# Sport_Analyzer_Chronojump_Teensy_4_4_but.net
KiCad netlist of a schematic drawn in EAGLE
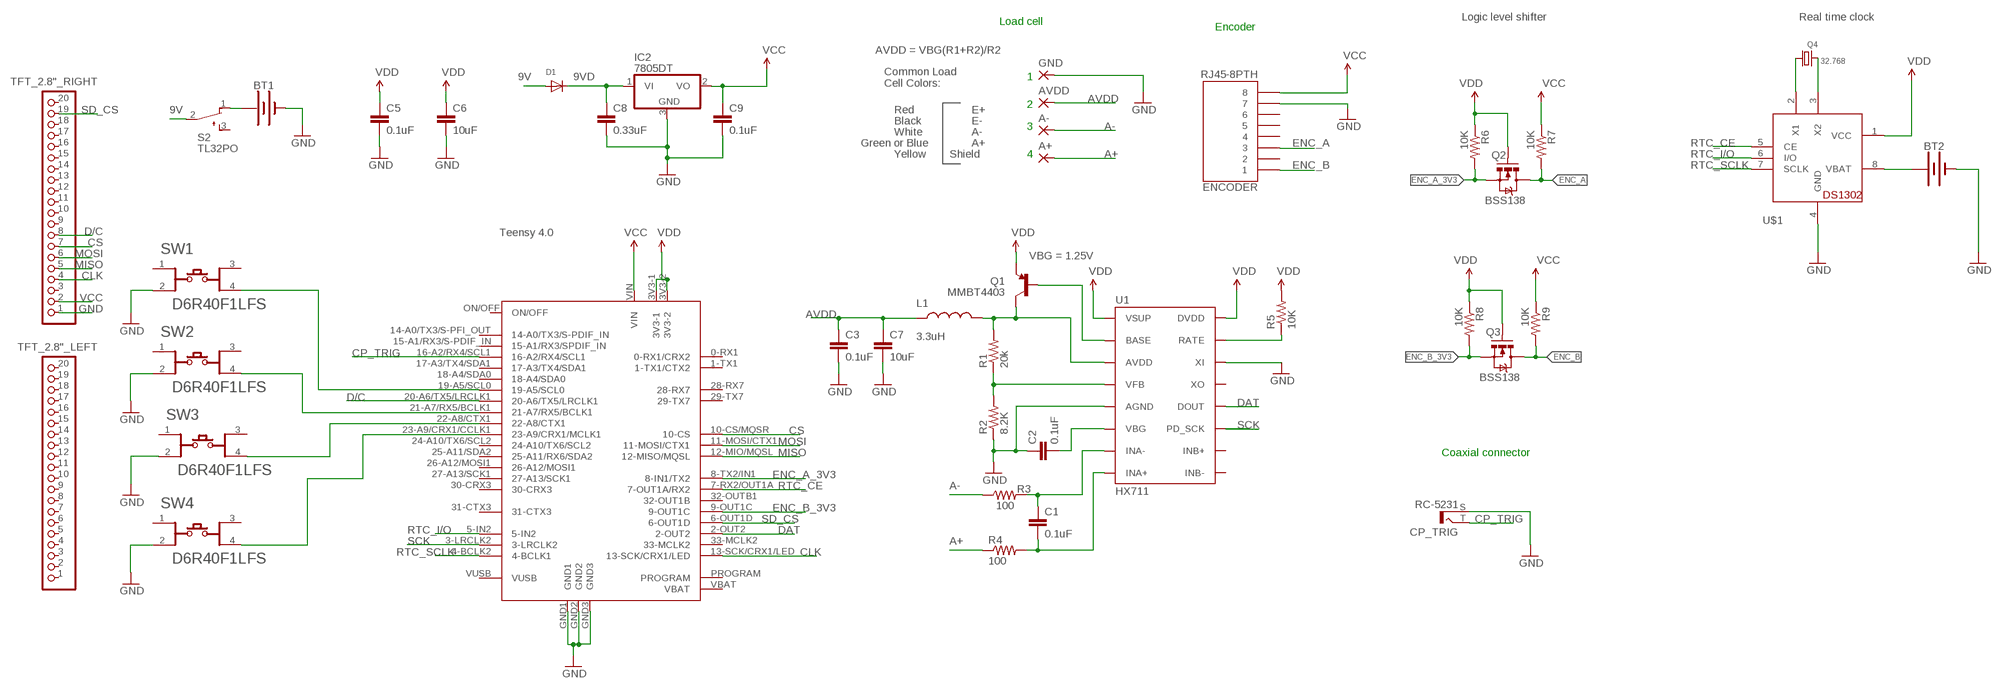
[diagram p0: schematic, sheet 1]

(export (version "E")
  (design (tool "Eeschema 10.0.6"))
  (components
    (comp (ref "A+")
      (value "3,81/1,4")
      (footprint "eagle-import:3,81_1,4")
      (libsource (lib "eagle-import") (part "3,81/1,4"))
    )
    (comp (ref "A-")
      (value "3,81/1,4")
      (footprint "eagle-import:3,81_1,4")
      (libsource (lib "eagle-import") (part "3,81/1,4"))
    )
    (comp (ref "AVDD")
      (value "3,81/1,4")
      (footprint "eagle-import:3,81_1,4")
      (libsource (lib "eagle-import") (part "3,81/1,4"))
    )
    (comp (ref "BT1")
      (value "BATTERY-9V")
      (footprint "eagle-import:BATTCON_9V")
      (libsource (lib "eagle-import") (part "BATTERY-9V"))
    )
    (comp (ref "BT2")
      (value "BATTERY-12MM_SMD")
      (footprint "eagle-import:BATTCON_12MM")
      (libsource (lib "eagle-import") (part "BATTERY-12MM_SMD"))
    )
    (comp (ref "C1")
      (value "0.1uF")
      (footprint "eagle-import:0603-CAP")
      (libsource (lib "eagle-import") (part "0.1UF-25V-5%(0603)"))
    )
    (comp (ref "C2")
      (value "0.1uF")
      (footprint "eagle-import:0603-CAP")
      (libsource (lib "eagle-import") (part "0.1UF-25V-5%(0603)"))
    )
    (comp (ref "C3")
      (value "0.1uF")
      (footprint "eagle-import:0603-CAP")
      (libsource (lib "eagle-import") (part "0.1UF-25V-5%(0603)"))
    )
    (comp (ref "C5")
      (value "0.1uF")
      (footprint "eagle-import:0603-CAP")
      (libsource (lib "eagle-import") (part "0.1UF-25V-5%(0603)"))
    )
    (comp (ref "C6")
      (value "10uF")
      (footprint "eagle-import:1210")
      (libsource (lib "eagle-import") (part "10UF50V20%(1210)"))
    )
    (comp (ref "C7")
      (value "10uF")
      (footprint "eagle-import:1210")
      (libsource (lib "eagle-import") (part "10UF50V20%(1210)"))
    )
    (comp (ref "C8")
      (value "0.33uF")
      (footprint "eagle-import:0603-CAP")
      (libsource (lib "eagle-import") (part "0.1UF-25V-5%(0603)"))
    )
    (comp (ref "C9")
      (value "0.1uF")
      (footprint "eagle-import:0603-CAP")
      (libsource (lib "eagle-import") (part "0.1UF-25V-5%(0603)"))
    )
    (comp (ref "CP_TRIG")
      (value "RC-5231")
      (footprint "eagle-import:RC-5231")
      (libsource (lib "eagle-import") (part "RC-5231"))
    )
    (comp (ref "D1")
      (value "DIODESOD-123")
      (footprint "eagle-import:SOD-123")
      (libsource (lib "eagle-import") (part "DIODESOD-123"))
    )
    (comp (ref "ENCODER")
      (value "RJ45-8PTH")
      (footprint "eagle-import:RJ45-8")
      (libsource (lib "eagle-import") (part "RJ45-8PTH"))
    )
    (comp (ref "GND")
      (value "3,81/1,4")
      (footprint "eagle-import:3,81_1,4")
      (libsource (lib "eagle-import") (part "3,81/1,4"))
    )
    (comp (ref "IC2")
      (value "7805DT")
      (footprint "eagle-import:TO252")
      (libsource (lib "eagle-import") (part "78DT05"))
    )
    (comp (ref "L1")
      (value "3.3uH")
      (footprint "eagle-import:0805")
      (libsource (lib "eagle-import") (part "INDUCTOR0805-IND"))
    )
    (comp (ref "Q1")
      (value "MMBT4403")
      (footprint "eagle-import:SOT23-3")
      (libsource (lib "eagle-import") (part "TRANSISTOR_PNPMMBT4403"))
    )
    (comp (ref "Q2")
      (value "BSS138")
      (footprint "eagle-import:SOT23-3")
      (libsource (lib "eagle-import") (part "MOSFET-NCHANNELSMD"))
    )
    (comp (ref "Q3")
      (value "BSS138")
      (footprint "eagle-import:SOT23-3")
      (libsource (lib "eagle-import") (part "MOSFET-NCHANNELSMD"))
    )
    (comp (ref "Q4")
      (value "32.768")
      (footprint "eagle-import:CRYSTAL_8X3.8")
      (libsource (lib "eagle-import") (part "CRYSTAL8.0X3.8"))
    )
    (comp (ref "R1")
      (value "20k")
      (footprint "eagle-import:0603-RES")
      (libsource (lib "eagle-import") (part "20KOHM1/10W1%(0603)"))
    )
    (comp (ref "R2")
      (value "8.2K")
      (footprint "eagle-import:0603-RES")
      (libsource (lib "eagle-import") (part "8.2KOHM-1/10W-5%(0603)"))
    )
    (comp (ref "R3")
      (value "100")
      (footprint "eagle-import:0603-RES")
      (libsource (lib "eagle-import") (part "100OHM-1/10W-1%(0603)"))
    )
    (comp (ref "R4")
      (value "100")
      (footprint "eagle-import:0603-RES")
      (libsource (lib "eagle-import") (part "100OHM-1/10W-1%(0603)"))
    )
    (comp (ref "R5")
      (value "10K")
      (footprint "eagle-import:0603-RES")
      (libsource (lib "eagle-import") (part "10KOHM-1/10W-1%(0603)0603"))
    )
    (comp (ref "R6")
      (value "10K")
      (footprint "eagle-import:0603-RES")
      (libsource (lib "eagle-import") (part "RESISTOR0603-RES"))
    )
    (comp (ref "R7")
      (value "10K")
      (footprint "eagle-import:0603-RES")
      (libsource (lib "eagle-import") (part "RESISTOR0603-RES"))
    )
    (comp (ref "R8")
      (value "10K")
      (footprint "eagle-import:0603-RES")
      (libsource (lib "eagle-import") (part "RESISTOR0603-RES"))
    )
    (comp (ref "R9")
      (value "10K")
      (footprint "eagle-import:0603-RES")
      (libsource (lib "eagle-import") (part "RESISTOR0603-RES"))
    )
    (comp (ref "S2")
      (value "TL32PO")
      (footprint "eagle-import:TL3XPO")
      (libsource (lib "eagle-import") (part "TL32PO"))
    )
    (comp (ref "SW1")
      (value "C&K_COMPONENTS_D6R40F1LFSC&K_COMPONENTS_D6R40F1LFS_0_0")
      (footprint "eagle-import:C&K_COMPONENTS_D6R40F1LFS_0")
      (fields
        (field (name "DIGIKEY_PART_NUMBER") "401-1975-ND")
        (field (name "MF") "C&K Components")
        (field (name "MOUSER_PART_NUMBER") "611-D6R40F1LFS")
      )
      (libsource (lib "eagle-import") (part "C&K_COMPONENTS_D6R40F1LFSC&K_COMPONENTS_D6R40F1LFS_0_0"))
    )
    (comp (ref "SW2")
      (value "C&K_COMPONENTS_D6R40F1LFSC&K_COMPONENTS_D6R40F1LFS_0_0")
      (footprint "eagle-import:C&K_COMPONENTS_D6R40F1LFS_0")
      (fields
        (field (name "DIGIKEY_PART_NUMBER") "401-1975-ND")
        (field (name "MF") "C&K Components")
        (field (name "MOUSER_PART_NUMBER") "611-D6R40F1LFS")
      )
      (libsource (lib "eagle-import") (part "C&K_COMPONENTS_D6R40F1LFSC&K_COMPONENTS_D6R40F1LFS_0_0"))
    )
    (comp (ref "SW3")
      (value "C&K_COMPONENTS_D6R40F1LFSC&K_COMPONENTS_D6R40F1LFS_0_0")
      (footprint "eagle-import:C&K_COMPONENTS_D6R40F1LFS_0")
      (fields
        (field (name "DIGIKEY_PART_NUMBER") "401-1975-ND")
        (field (name "MF") "C&K Components")
        (field (name "MOUSER_PART_NUMBER") "611-D6R40F1LFS")
      )
      (libsource (lib "eagle-import") (part "C&K_COMPONENTS_D6R40F1LFSC&K_COMPONENTS_D6R40F1LFS_0_0"))
    )
    (comp (ref "SW4")
      (value "C&K_COMPONENTS_D6R40F1LFSC&K_COMPONENTS_D6R40F1LFS_0_0")
      (footprint "eagle-import:C&K_COMPONENTS_D6R40F1LFS_0")
      (fields
        (field (name "DIGIKEY_PART_NUMBER") "401-1975-ND")
        (field (name "MF") "C&K Components")
        (field (name "MOUSER_PART_NUMBER") "611-D6R40F1LFS")
      )
      (libsource (lib "eagle-import") (part "C&K_COMPONENTS_D6R40F1LFSC&K_COMPONENTS_D6R40F1LFS_0_0"))
    )
    (comp (ref "TFT_2.8\"_LEFT")
      (value "PINHD-1X20")
      (footprint "eagle-import:1X20")
      (libsource (lib "eagle-import") (part "PINHD-1X20"))
    )
    (comp (ref "TFT_2.8\"_RIGHT")
      (value "PINHD-1X20")
      (footprint "eagle-import:1X20")
      (libsource (lib "eagle-import") (part "PINHD-1X20"))
    )
    (comp (ref "U$1")
      (value "DS1302")
      (footprint "eagle-import:DIL08-ROUND")
      (libsource (lib "eagle-import") (part "DS1302"))
    )
    (comp (ref "U$2")
      (value "TEENSY40")
      (footprint "eagle-import:TEENSY40")
      (libsource (lib "eagle-import") (part "TEENSY40"))
    )
    (comp (ref "U1")
      (value "HX711")
      (footprint "eagle-import:SO16")
      (libsource (lib "eagle-import") (part "HX711HX711"))
    )
  )
  (nets
    (net (code "1") (name "/9V") (class "Default")
      (node (ref "D1") (pin "A") (pinfunction "A_A") (pintype "passive"))
      (node (ref "S2") (pin "2") (pinfunction "P_2") (pintype "passive"))
    )
    (net (code "2") (name "/9VD") (class "Default")
      (node (ref "C8") (pin "1") (pinfunction "1_1") (pintype "passive"))
      (node (ref "D1") (pin "C") (pinfunction "C_C") (pintype "passive"))
      (node (ref "IC2") (pin "1") (pinfunction "VI_1") (pintype "input"))
    )
    (net (code "3") (name "/A+") (class "Default")
      (node (ref "A+") (pin "1") (pinfunction "P_1") (pintype "passive"))
      (node (ref "R4") (pin "1") (pinfunction "1_1") (pintype "passive"))
    )
    (net (code "4") (name "/A-") (class "Default")
      (node (ref "A-") (pin "1") (pinfunction "P_1") (pintype "passive"))
      (node (ref "R3") (pin "1") (pinfunction "1_1") (pintype "passive"))
    )
    (net (code "5") (name "/AVDD") (class "Default")
      (node (ref "AVDD") (pin "1") (pinfunction "P_1") (pintype "passive"))
      (node (ref "C3") (pin "1") (pinfunction "1_1") (pintype "passive"))
      (node (ref "C7") (pin "1") (pinfunction "1_1") (pintype "passive"))
      (node (ref "L1") (pin "1") (pinfunction "1_1") (pintype "passive"))
    )
    (net (code "6") (name "/CLK") (class "Default")
      (node (ref "TFT_2.8\"_RIGHT") (pin "4") (pinfunction "4_4") (pintype "passive"))
      (node (ref "U$2") (pin "13-SCK/CRX1/LED") (pinfunction "13-SCK/CRX1/LED_13-SCK/CRX1/LED") (pintype "bidirectional"))
    )
    (net (code "7") (name "/CP_TRIG") (class "Default")
      (node (ref "CP_TRIG") (pin "T") (pinfunction "T_T") (pintype "passive"))
      (node (ref "U$2") (pin "16-A2/RX4/SCL1") (pinfunction "16-A2/RX4/SCL1_16-A2/RX4/SCL1") (pintype "bidirectional"))
    )
    (net (code "8") (name "/CS") (class "Default")
      (node (ref "TFT_2.8\"_RIGHT") (pin "7") (pinfunction "7_7") (pintype "passive"))
      (node (ref "U$2") (pin "10-CS/MQSR") (pinfunction "10-CS_10-CS/MQSR") (pintype "bidirectional"))
    )
    (net (code "9") (name "/DAT") (class "Default")
      (node (ref "U$2") (pin "2-OUT2") (pinfunction "2-OUT2_2-OUT2") (pintype "bidirectional"))
      (node (ref "U1") (pin "12") (pinfunction "DOUT_12") (pintype "bidirectional"))
    )
    (net (code "10") (name "/D{slash}C") (class "Default")
      (node (ref "TFT_2.8\"_RIGHT") (pin "8") (pinfunction "8_8") (pintype "passive"))
      (node (ref "U$2") (pin "20-A6/TX5/LRCLK1") (pinfunction "20-A6/TX5/LRCLK1_20-A6/TX5/LRCLK1") (pintype "bidirectional"))
    )
    (net (code "11") (name "/MISO") (class "Default")
      (node (ref "TFT_2.8\"_RIGHT") (pin "5") (pinfunction "5_5") (pintype "passive"))
      (node (ref "U$2") (pin "12-MIO/MQSL") (pinfunction "12-MISO/MQSL_12-MIO/MQSL") (pintype "bidirectional"))
    )
    (net (code "12") (name "/MOSI") (class "Default")
      (node (ref "TFT_2.8\"_RIGHT") (pin "6") (pinfunction "6_6") (pintype "passive"))
      (node (ref "U$2") (pin "11-MOSI/CTX1") (pinfunction "11-MOSI/CTX1_11-MOSI/CTX1") (pintype "bidirectional"))
    )
    (net (code "13") (name "/RTC_CE") (class "Default")
      (node (ref "U$1") (pin "5") (pinfunction "CE_5") (pintype "input"))
      (node (ref "U$2") (pin "7-RX2/OUT1A") (pinfunction "7-OUT1A/RX2_7-RX2/OUT1A") (pintype "bidirectional"))
    )
    (net (code "14") (name "/RTC_I{slash}O") (class "Default")
      (node (ref "U$1") (pin "6") (pinfunction "I/O_6") (pintype "bidirectional"))
      (node (ref "U$2") (pin "5-IN2") (pinfunction "5-IN2_5-IN2") (pintype "bidirectional"))
    )
    (net (code "15") (name "/RTC_SCLK") (class "Default")
      (node (ref "U$1") (pin "7") (pinfunction "SCLK_7") (pintype "input"))
      (node (ref "U$2") (pin "4-BCLK2") (pinfunction "4-BCLK1_4-BCLK2") (pintype "bidirectional"))
    )
    (net (code "16") (name "/SCK") (class "Default")
      (node (ref "U$2") (pin "3-LRCLK2") (pinfunction "3-LRCLK2_3-LRCLK2") (pintype "bidirectional"))
      (node (ref "U1") (pin "11") (pinfunction "PD_SCK_11") (pintype "bidirectional"))
    )
    (net (code "17") (name "/SD_CS") (class "Default")
      (node (ref "TFT_2.8\"_RIGHT") (pin "19") (pinfunction "19_19") (pintype "passive"))
      (node (ref "U$2") (pin "6-OUT1D") (pinfunction "6-OUT1D_6-OUT1D") (pintype "bidirectional"))
    )
    (net (code "18") (name "ENC_A") (class "Default")
      (node (ref "ENCODER") (pin "3") (pinfunction "3_3") (pintype "bidirectional"))
      (node (ref "Q2") (pin "3") (pinfunction "D_3") (pintype "passive"))
      (node (ref "R7") (pin "2") (pinfunction "2_2") (pintype "passive"))
    )
    (net (code "19") (name "ENC_A_3V3") (class "Default")
      (node (ref "Q2") (pin "2") (pinfunction "S_2") (pintype "passive"))
      (node (ref "R6") (pin "2") (pinfunction "2_2") (pintype "passive"))
      (node (ref "U$2") (pin "8-TX2/IN1") (pinfunction "8-IN1/TX2_8-TX2/IN1") (pintype "bidirectional"))
    )
    (net (code "20") (name "ENC_B") (class "Default")
      (node (ref "ENCODER") (pin "1") (pinfunction "1_1") (pintype "bidirectional"))
      (node (ref "Q3") (pin "3") (pinfunction "D_3") (pintype "passive"))
      (node (ref "R9") (pin "2") (pinfunction "2_2") (pintype "passive"))
    )
    (net (code "21") (name "ENC_B_3V3") (class "Default")
      (node (ref "Q3") (pin "2") (pinfunction "S_2") (pintype "passive"))
      (node (ref "R8") (pin "2") (pinfunction "2_2") (pintype "passive"))
      (node (ref "U$2") (pin "9-OUT1C") (pinfunction "9-OUT1C_9-OUT1C") (pintype "bidirectional"))
    )
    (net (code "22") (name "GND") (class "Default")
      (node (ref "BT1") (pin "-") (pinfunction "-_-") (pintype "power_in"))
      (node (ref "BT2") (pin "GND") (pinfunction "-_GND") (pintype "power_in"))
      (node (ref "C2") (pin "1") (pinfunction "1_1") (pintype "passive"))
      (node (ref "C3") (pin "2") (pinfunction "2_2") (pintype "passive"))
      (node (ref "C5") (pin "2") (pinfunction "2_2") (pintype "passive"))
      (node (ref "C6") (pin "2") (pinfunction "2_2") (pintype "passive"))
      (node (ref "C7") (pin "2") (pinfunction "2_2") (pintype "passive"))
      (node (ref "C8") (pin "2") (pinfunction "2_2") (pintype "passive"))
      (node (ref "C9") (pin "2") (pinfunction "2_2") (pintype "passive"))
      (node (ref "CP_TRIG") (pin "S") (pinfunction "S_S") (pintype "passive"))
      (node (ref "ENCODER") (pin "7") (pinfunction "7_7") (pintype "bidirectional"))
      (node (ref "GND") (pin "1") (pinfunction "P_1") (pintype "passive"))
      (node (ref "IC2") (pin "3") (pinfunction "GND_3") (pintype "passive"))
      (node (ref "R2") (pin "1") (pinfunction "1_1") (pintype "passive"))
      (node (ref "SW1") (pin "2") (pinfunction "2_2") (pintype "passive"))
      (node (ref "SW2") (pin "2") (pinfunction "2_2") (pintype "passive"))
      (node (ref "SW3") (pin "2") (pinfunction "2_2") (pintype "passive"))
      (node (ref "SW4") (pin "2") (pinfunction "2_2") (pintype "passive"))
      (node (ref "TFT_2.8\"_RIGHT") (pin "1") (pinfunction "1_1") (pintype "passive"))
      (node (ref "U$1") (pin "4") (pinfunction "GND_4") (pintype "power_in"))
      (node (ref "U$2") (pin "GND1") (pinfunction "GND1_GND1") (pintype "bidirectional"))
      (node (ref "U$2") (pin "GND2") (pinfunction "GND2_GND2") (pintype "bidirectional"))
      (node (ref "U$2") (pin "GND3") (pinfunction "GND3_GND3") (pintype "bidirectional"))
      (node (ref "U1") (pin "14") (pinfunction "XI_14") (pintype "bidirectional"))
      (node (ref "U1") (pin "5") (pinfunction "AGND_5") (pintype "bidirectional"))
    )
    (net (code "23") (name "Net-(BT2-+)") (class "Default")
      (node (ref "BT2") (pin "PWR@1") (pinfunction "+_PWR@1") (pintype "power_in"))
      (node (ref "U$1") (pin "8") (pinfunction "VBAT_8") (pintype "power_in"))
    )
    (net (code "24") (name "Net-(Q1-B)") (class "Default")
      (node (ref "Q1") (pin "1") (pinfunction "B_1") (pintype "passive"))
      (node (ref "U1") (pin "2") (pinfunction "BASE_2") (pintype "bidirectional"))
    )
    (net (code "25") (name "Net-(Q1-C)") (class "Default")
      (node (ref "L1") (pin "2") (pinfunction "2_2") (pintype "passive"))
      (node (ref "Q1") (pin "3") (pinfunction "C_3") (pintype "passive"))
      (node (ref "R1") (pin "2") (pinfunction "2_2") (pintype "passive"))
      (node (ref "U1") (pin "3") (pinfunction "AVDD_3") (pintype "bidirectional"))
    )
    (net (code "26") (name "Net-(Q4-1)") (class "Default")
      (node (ref "Q4") (pin "P$1") (pinfunction "1_P$1") (pintype "passive"))
      (node (ref "U$1") (pin "3") (pinfunction "X2_3") (pintype "passive"))
    )
    (net (code "27") (name "Net-(Q4-2)") (class "Default")
      (node (ref "Q4") (pin "P$4") (pinfunction "2_P$4") (pintype "passive"))
      (node (ref "U$1") (pin "2") (pinfunction "X1_2") (pintype "passive"))
    )
    (net (code "28") (name "Net-(S2-O)") (class "Default")
      (node (ref "BT1") (pin "+") (pinfunction "+_+") (pintype "power_in"))
      (node (ref "S2") (pin "1") (pinfunction "O_1") (pintype "passive"))
    )
    (net (code "29") (name "Net-(SW1-Pad4)") (class "Default")
      (node (ref "SW1") (pin "4") (pinfunction "4_4") (pintype "passive"))
      (node (ref "U$2") (pin "19-A5/SCL0") (pinfunction "19-A5/SCL0_19-A5/SCL0") (pintype "bidirectional"))
    )
    (net (code "30") (name "Net-(SW2-Pad4)") (class "Default")
      (node (ref "SW2") (pin "4") (pinfunction "4_4") (pintype "passive"))
      (node (ref "U$2") (pin "21-A7/RX5/BCLK1") (pinfunction "21-A7/RX5/BCLK1_21-A7/RX5/BCLK1") (pintype "bidirectional"))
    )
    (net (code "31") (name "Net-(SW3-Pad4)") (class "Default")
      (node (ref "SW3") (pin "4") (pinfunction "4_4") (pintype "passive"))
      (node (ref "U$2") (pin "22-A8/CTX1") (pinfunction "22-A8/CTX1_22-A8/CTX1") (pintype "bidirectional"))
    )
    (net (code "32") (name "Net-(U$2-23-A9{slash}CRX1{slash}MCLK1)") (class "Default")
      (node (ref "SW4") (pin "4") (pinfunction "4_4") (pintype "passive"))
      (node (ref "U$2") (pin "23-A9/CRX1/CCLK1") (pinfunction "23-A9/CRX1/MCLK1_23-A9/CRX1/CCLK1") (pintype "bidirectional"))
    )
    (net (code "33") (name "Net-(U1-INA+)") (class "Default")
      (node (ref "C1") (pin "2") (pinfunction "2_2") (pintype "passive"))
      (node (ref "R4") (pin "2") (pinfunction "2_2") (pintype "passive"))
      (node (ref "U1") (pin "8") (pinfunction "INA+_8") (pintype "bidirectional"))
    )
    (net (code "34") (name "Net-(U1-INA-)") (class "Default")
      (node (ref "C1") (pin "1") (pinfunction "1_1") (pintype "passive"))
      (node (ref "R3") (pin "2") (pinfunction "2_2") (pintype "passive"))
      (node (ref "U1") (pin "7") (pinfunction "INA-_7") (pintype "bidirectional"))
    )
    (net (code "35") (name "Net-(U1-RATE)") (class "Default")
      (node (ref "R5") (pin "1") (pinfunction "1_1") (pintype "passive"))
      (node (ref "U1") (pin "15") (pinfunction "RATE_15") (pintype "bidirectional"))
    )
    (net (code "36") (name "Net-(U1-VBG)") (class "Default")
      (node (ref "C2") (pin "2") (pinfunction "2_2") (pintype "passive"))
      (node (ref "U1") (pin "6") (pinfunction "VBG_6") (pintype "bidirectional"))
    )
    (net (code "37") (name "Net-(U1-VFB)") (class "Default")
      (node (ref "R1") (pin "1") (pinfunction "1_1") (pintype "passive"))
      (node (ref "R2") (pin "2") (pinfunction "2_2") (pintype "passive"))
      (node (ref "U1") (pin "4") (pinfunction "VFB_4") (pintype "bidirectional"))
    )
    (net (code "38") (name "VCC") (class "Default")
      (node (ref "C9") (pin "1") (pinfunction "1_1") (pintype "passive"))
      (node (ref "ENCODER") (pin "8") (pinfunction "8_8") (pintype "bidirectional"))
      (node (ref "IC2") (pin "2") (pinfunction "VO_2") (pintype "passive"))
      (node (ref "R7") (pin "1") (pinfunction "1_1") (pintype "passive"))
      (node (ref "R9") (pin "1") (pinfunction "1_1") (pintype "passive"))
      (node (ref "TFT_2.8\"_RIGHT") (pin "2") (pinfunction "2_2") (pintype "passive"))
      (node (ref "U$2") (pin "VIN") (pinfunction "VIN_VIN") (pintype "bidirectional"))
    )
    (net (code "39") (name "VDD") (class "Default")
      (node (ref "C5") (pin "1") (pinfunction "1_1") (pintype "passive"))
      (node (ref "C6") (pin "1") (pinfunction "1_1") (pintype "passive"))
      (node (ref "Q1") (pin "2") (pinfunction "E_2") (pintype "passive"))
      (node (ref "Q2") (pin "1") (pinfunction "G_1") (pintype "passive"))
      (node (ref "Q3") (pin "1") (pinfunction "G_1") (pintype "passive"))
      (node (ref "R5") (pin "2") (pinfunction "2_2") (pintype "passive"))
      (node (ref "R6") (pin "1") (pinfunction "1_1") (pintype "passive"))
      (node (ref "R8") (pin "1") (pinfunction "1_1") (pintype "passive"))
      (node (ref "U$1") (pin "1") (pinfunction "VCC_1") (pintype "power_in"))
      (node (ref "U$2") (pin "3V3-1") (pinfunction "3V3-1_3V3-1") (pintype "bidirectional"))
      (node (ref "U$2") (pin "3V3-2") (pinfunction "3V3-2_3V3-2") (pintype "bidirectional"))
      (node (ref "U1") (pin "1") (pinfunction "VSUP_1") (pintype "bidirectional"))
      (node (ref "U1") (pin "16") (pinfunction "DVDD_16") (pintype "bidirectional"))
    )
    (net (code "40") (name "unconnected-(ENCODER-Pad2)") (class "Default")
      (node (ref "ENCODER") (pin "2") (pinfunction "2_2") (pintype "bidirectional"))
    )
    (net (code "41") (name "unconnected-(ENCODER-Pad4)") (class "Default")
      (node (ref "ENCODER") (pin "4") (pinfunction "4_4") (pintype "bidirectional"))
    )
    (net (code "42") (name "unconnected-(ENCODER-Pad5)") (class "Default")
      (node (ref "ENCODER") (pin "5") (pinfunction "5_5") (pintype "bidirectional"))
    )
    (net (code "43") (name "unconnected-(ENCODER-Pad6)") (class "Default")
      (node (ref "ENCODER") (pin "6") (pinfunction "6_6") (pintype "bidirectional"))
    )
    (net (code "44") (name "unconnected-(S2-S-Pad3)") (class "Default")
      (node (ref "S2") (pin "3") (pinfunction "S_3") (pintype "passive"))
    )
    (net (code "45") (name "unconnected-(SW1-Pad1)") (class "Default")
      (node (ref "SW1") (pin "1") (pinfunction "1_1") (pintype "passive"))
    )
    (net (code "46") (name "unconnected-(SW1-Pad3)") (class "Default")
      (node (ref "SW1") (pin "3") (pinfunction "3_3") (pintype "passive"))
    )
    (net (code "47") (name "unconnected-(SW2-Pad1)") (class "Default")
      (node (ref "SW2") (pin "1") (pinfunction "1_1") (pintype "passive"))
    )
    (net (code "48") (name "unconnected-(SW2-Pad3)") (class "Default")
      (node (ref "SW2") (pin "3") (pinfunction "3_3") (pintype "passive"))
    )
    (net (code "49") (name "unconnected-(SW3-Pad1)") (class "Default")
      (node (ref "SW3") (pin "1") (pinfunction "1_1") (pintype "passive"))
    )
    (net (code "50") (name "unconnected-(SW3-Pad3)") (class "Default")
      (node (ref "SW3") (pin "3") (pinfunction "3_3") (pintype "passive"))
    )
    (net (code "51") (name "unconnected-(SW4-Pad1)") (class "Default")
      (node (ref "SW4") (pin "1") (pinfunction "1_1") (pintype "passive"))
    )
    (net (code "52") (name "unconnected-(SW4-Pad3)") (class "Default")
      (node (ref "SW4") (pin "3") (pinfunction "3_3") (pintype "passive"))
    )
    (net (code "53") (name "unconnected-(TFT_2.8\"_LEFT-Pad1)") (class "Default")
      (node (ref "TFT_2.8\"_LEFT") (pin "1") (pinfunction "1_1") (pintype "passive"))
    )
    (net (code "54") (name "unconnected-(TFT_2.8\"_LEFT-Pad2)") (class "Default")
      (node (ref "TFT_2.8\"_LEFT") (pin "2") (pinfunction "2_2") (pintype "passive"))
    )
    (net (code "55") (name "unconnected-(TFT_2.8\"_LEFT-Pad3)") (class "Default")
      (node (ref "TFT_2.8\"_LEFT") (pin "3") (pinfunction "3_3") (pintype "passive"))
    )
    (net (code "56") (name "unconnected-(TFT_2.8\"_LEFT-Pad4)") (class "Default")
      (node (ref "TFT_2.8\"_LEFT") (pin "4") (pinfunction "4_4") (pintype "passive"))
    )
    (net (code "57") (name "unconnected-(TFT_2.8\"_LEFT-Pad5)") (class "Default")
      (node (ref "TFT_2.8\"_LEFT") (pin "5") (pinfunction "5_5") (pintype "passive"))
    )
    (net (code "58") (name "unconnected-(TFT_2.8\"_LEFT-Pad6)") (class "Default")
      (node (ref "TFT_2.8\"_LEFT") (pin "6") (pinfunction "6_6") (pintype "passive"))
    )
    (net (code "59") (name "unconnected-(TFT_2.8\"_LEFT-Pad7)") (class "Default")
      (node (ref "TFT_2.8\"_LEFT") (pin "7") (pinfunction "7_7") (pintype "passive"))
    )
    (net (code "60") (name "unconnected-(TFT_2.8\"_LEFT-Pad8)") (class "Default")
      (node (ref "TFT_2.8\"_LEFT") (pin "8") (pinfunction "8_8") (pintype "passive"))
    )
    (net (code "61") (name "unconnected-(TFT_2.8\"_LEFT-Pad9)") (class "Default")
      (node (ref "TFT_2.8\"_LEFT") (pin "9") (pinfunction "9_9") (pintype "passive"))
    )
    (net (code "62") (name "unconnected-(TFT_2.8\"_LEFT-Pad10)") (class "Default")
      (node (ref "TFT_2.8\"_LEFT") (pin "10") (pinfunction "10_10") (pintype "passive"))
    )
    (net (code "63") (name "unconnected-(TFT_2.8\"_LEFT-Pad11)") (class "Default")
      (node (ref "TFT_2.8\"_LEFT") (pin "11") (pinfunction "11_11") (pintype "passive"))
    )
    (net (code "64") (name "unconnected-(TFT_2.8\"_LEFT-Pad12)") (class "Default")
      (node (ref "TFT_2.8\"_LEFT") (pin "12") (pinfunction "12_12") (pintype "passive"))
    )
    (net (code "65") (name "unconnected-(TFT_2.8\"_LEFT-Pad13)") (class "Default")
      (node (ref "TFT_2.8\"_LEFT") (pin "13") (pinfunction "13_13") (pintype "passive"))
    )
    (net (code "66") (name "unconnected-(TFT_2.8\"_LEFT-Pad14)") (class "Default")
      (node (ref "TFT_2.8\"_LEFT") (pin "14") (pinfunction "14_14") (pintype "passive"))
    )
    (net (code "67") (name "unconnected-(TFT_2.8\"_LEFT-Pad15)") (class "Default")
      (node (ref "TFT_2.8\"_LEFT") (pin "15") (pinfunction "15_15") (pintype "passive"))
    )
    (net (code "68") (name "unconnected-(TFT_2.8\"_LEFT-Pad16)") (class "Default")
      (node (ref "TFT_2.8\"_LEFT") (pin "16") (pinfunction "16_16") (pintype "passive"))
    )
    (net (code "69") (name "unconnected-(TFT_2.8\"_LEFT-Pad17)") (class "Default")
      (node (ref "TFT_2.8\"_LEFT") (pin "17") (pinfunction "17_17") (pintype "passive"))
    )
    (net (code "70") (name "unconnected-(TFT_2.8\"_LEFT-Pad18)") (class "Default")
      (node (ref "TFT_2.8\"_LEFT") (pin "18") (pinfunction "18_18") (pintype "passive"))
    )
    (net (code "71") (name "unconnected-(TFT_2.8\"_LEFT-Pad19)") (class "Default")
      (node (ref "TFT_2.8\"_LEFT") (pin "19") (pinfunction "19_19") (pintype "passive"))
    )
    (net (code "72") (name "unconnected-(TFT_2.8\"_LEFT-Pad20)") (class "Default")
      (node (ref "TFT_2.8\"_LEFT") (pin "20") (pinfunction "20_20") (pintype "passive"))
    )
    (net (code "73") (name "unconnected-(TFT_2.8\"_RIGHT-Pad3)") (class "Default")
      (node (ref "TFT_2.8\"_RIGHT") (pin "3") (pinfunction "3_3") (pintype "passive"))
    )
    (net (code "74") (name "unconnected-(TFT_2.8\"_RIGHT-Pad9)") (class "Default")
      (node (ref "TFT_2.8\"_RIGHT") (pin "9") (pinfunction "9_9") (pintype "passive"))
    )
    (net (code "75") (name "unconnected-(TFT_2.8\"_RIGHT-Pad10)") (class "Default")
      (node (ref "TFT_2.8\"_RIGHT") (pin "10") (pinfunction "10_10") (pintype "passive"))
    )
    (net (code "76") (name "unconnected-(TFT_2.8\"_RIGHT-Pad11)") (class "Default")
      (node (ref "TFT_2.8\"_RIGHT") (pin "11") (pinfunction "11_11") (pintype "passive"))
    )
    (net (code "77") (name "unconnected-(TFT_2.8\"_RIGHT-Pad12)") (class "Default")
      (node (ref "TFT_2.8\"_RIGHT") (pin "12") (pinfunction "12_12") (pintype "passive"))
    )
    (net (code "78") (name "unconnected-(TFT_2.8\"_RIGHT-Pad13)") (class "Default")
      (node (ref "TFT_2.8\"_RIGHT") (pin "13") (pinfunction "13_13") (pintype "passive"))
    )
    (net (code "79") (name "unconnected-(TFT_2.8\"_RIGHT-Pad14)") (class "Default")
      (node (ref "TFT_2.8\"_RIGHT") (pin "14") (pinfunction "14_14") (pintype "passive"))
    )
    (net (code "80") (name "unconnected-(TFT_2.8\"_RIGHT-Pad15)") (class "Default")
      (node (ref "TFT_2.8\"_RIGHT") (pin "15") (pinfunction "15_15") (pintype "passive"))
    )
    (net (code "81") (name "unconnected-(TFT_2.8\"_RIGHT-Pad16)") (class "Default")
      (node (ref "TFT_2.8\"_RIGHT") (pin "16") (pinfunction "16_16") (pintype "passive"))
    )
    (net (code "82") (name "unconnected-(TFT_2.8\"_RIGHT-Pad17)") (class "Default")
      (node (ref "TFT_2.8\"_RIGHT") (pin "17") (pinfunction "17_17") (pintype "passive"))
    )
    (net (code "83") (name "unconnected-(TFT_2.8\"_RIGHT-Pad18)") (class "Default")
      (node (ref "TFT_2.8\"_RIGHT") (pin "18") (pinfunction "18_18") (pintype "passive"))
    )
    (net (code "84") (name "unconnected-(TFT_2.8\"_RIGHT-Pad20)") (class "Default")
      (node (ref "TFT_2.8\"_RIGHT") (pin "20") (pinfunction "20_20") (pintype "passive"))
    )
    (net (code "85") (name "unconnected-(U$2-0-RX1{slash}CRX2-Pad0-RX1)") (class "Default")
      (node (ref "U$2") (pin "0-RX1") (pinfunction "0-RX1/CRX2_0-RX1") (pintype "bidirectional"))
    )
    (net (code "86") (name "unconnected-(U$2-1-TX1{slash}CTX2-Pad1-TX1)") (class "Default")
      (node (ref "U$2") (pin "1-TX1") (pinfunction "1-TX1/CTX2_1-TX1") (pintype "bidirectional"))
    )
    (net (code "87") (name "unconnected-(U$2-14-A0{slash}TX3{slash}S-PDIF_IN-Pad14-A0{slash}TX3{slash}S-PFI_OUT)") (class "Default")
      (node (ref "U$2") (pin "14-A0/TX3/S-PFI_OUT") (pinfunction "14-A0/TX3/S-PDIF_IN_14-A0/TX3/S-PFI_OUT") (pintype "bidirectional"))
    )
    (net (code "88") (name "unconnected-(U$2-15-A1{slash}RX3{slash}SPDIF_IN-Pad15-A1{slash}RX3{slash}S-PDIF_IN)") (class "Default")
      (node (ref "U$2") (pin "15-A1/RX3/S-PDIF_IN") (pinfunction "15-A1/RX3/SPDIF_IN_15-A1/RX3/S-PDIF_IN") (pintype "bidirectional"))
    )
    (net (code "89") (name "unconnected-(U$2-25-A11{slash}RX6{slash}SDA2-Pad25-A11{slash}SDA2)") (class "Default")
      (node (ref "U$2") (pin "25-A11/SDA2") (pinfunction "25-A11/RX6/SDA2_25-A11/SDA2") (pintype "bidirectional"))
    )
    (net (code "90") (name "unconnected-(U$2-32-OUT1B-Pad32-OUTB1)") (class "Default")
      (node (ref "U$2") (pin "32-OUTB1") (pinfunction "32-OUT1B_32-OUTB1") (pintype "bidirectional"))
    )
    (net (code "91") (name "unconnected-(U$2-Pad17-A3{slash}TX4{slash}SDA1)") (class "Default")
      (node (ref "U$2") (pin "17-A3/TX4/SDA1") (pinfunction "17-A3/TX4/SDA1_17-A3/TX4/SDA1") (pintype "bidirectional"))
    )
    (net (code "92") (name "unconnected-(U$2-Pad18-A4{slash}SDA0)") (class "Default")
      (node (ref "U$2") (pin "18-A4/SDA0") (pinfunction "18-A4/SDA0_18-A4/SDA0") (pintype "bidirectional"))
    )
    (net (code "93") (name "unconnected-(U$2-Pad24-A10{slash}TX6{slash}SCL2)") (class "Default")
      (node (ref "U$2") (pin "24-A10/TX6/SCL2") (pinfunction "24-A10/TX6/SCL2_24-A10/TX6/SCL2") (pintype "bidirectional"))
    )
    (net (code "94") (name "unconnected-(U$2-Pad26-A12{slash}MOSI1)") (class "Default")
      (node (ref "U$2") (pin "26-A12/MOSI1") (pinfunction "26-A12/MOSI1_26-A12/MOSI1") (pintype "bidirectional"))
    )
    (net (code "95") (name "unconnected-(U$2-Pad27-A13{slash}SCK1)") (class "Default")
      (node (ref "U$2") (pin "27-A13/SCK1") (pinfunction "27-A13/SCK1_27-A13/SCK1") (pintype "bidirectional"))
    )
    (net (code "96") (name "unconnected-(U$2-Pad28-RX7)") (class "Default")
      (node (ref "U$2") (pin "28-RX7") (pinfunction "28-RX7_28-RX7") (pintype "bidirectional"))
    )
    (net (code "97") (name "unconnected-(U$2-Pad29-TX7)") (class "Default")
      (node (ref "U$2") (pin "29-TX7") (pinfunction "29-TX7_29-TX7") (pintype "bidirectional"))
    )
    (net (code "98") (name "unconnected-(U$2-Pad30-CRX3)") (class "Default")
      (node (ref "U$2") (pin "30-CRX3") (pinfunction "30-CRX3_30-CRX3") (pintype "bidirectional"))
    )
    (net (code "99") (name "unconnected-(U$2-Pad31-CTX3)") (class "Default")
      (node (ref "U$2") (pin "31-CTX3") (pinfunction "31-CTX3_31-CTX3") (pintype "bidirectional"))
    )
    (net (code "100") (name "unconnected-(U$2-Pad33-MCLK2)") (class "Default")
      (node (ref "U$2") (pin "33-MCLK2") (pinfunction "33-MCLK2_33-MCLK2") (pintype "bidirectional"))
    )
    (net (code "101") (name "unconnected-(U$2-PadON{slash}OFF)") (class "Default")
      (node (ref "U$2") (pin "ON/OFF") (pinfunction "ON/OFF_ON/OFF") (pintype "bidirectional"))
    )
    (net (code "102") (name "unconnected-(U$2-PadPROGRAM)") (class "Default")
      (node (ref "U$2") (pin "PROGRAM") (pinfunction "PROGRAM_PROGRAM") (pintype "bidirectional"))
    )
    (net (code "103") (name "unconnected-(U$2-PadVBAT)") (class "Default")
      (node (ref "U$2") (pin "VBAT") (pinfunction "VBAT_VBAT") (pintype "bidirectional"))
    )
    (net (code "104") (name "unconnected-(U$2-PadVUSB)") (class "Default")
      (node (ref "U$2") (pin "VUSB") (pinfunction "VUSB_VUSB") (pintype "bidirectional"))
    )
    (net (code "105") (name "unconnected-(U1-INB+-Pad10)") (class "Default")
      (node (ref "U1") (pin "10") (pinfunction "INB+_10") (pintype "bidirectional"))
    )
    (net (code "106") (name "unconnected-(U1-INB--Pad9)") (class "Default")
      (node (ref "U1") (pin "9") (pinfunction "INB-_9") (pintype "bidirectional"))
    )
    (net (code "107") (name "unconnected-(U1-XO-Pad13)") (class "Default")
      (node (ref "U1") (pin "13") (pinfunction "XO_13") (pintype "bidirectional"))
    )
  )
)
